# 105358-3SC001-01-A_PWR_MGMT.net
KiCad netlist of a schematic drawn in Altium Designer
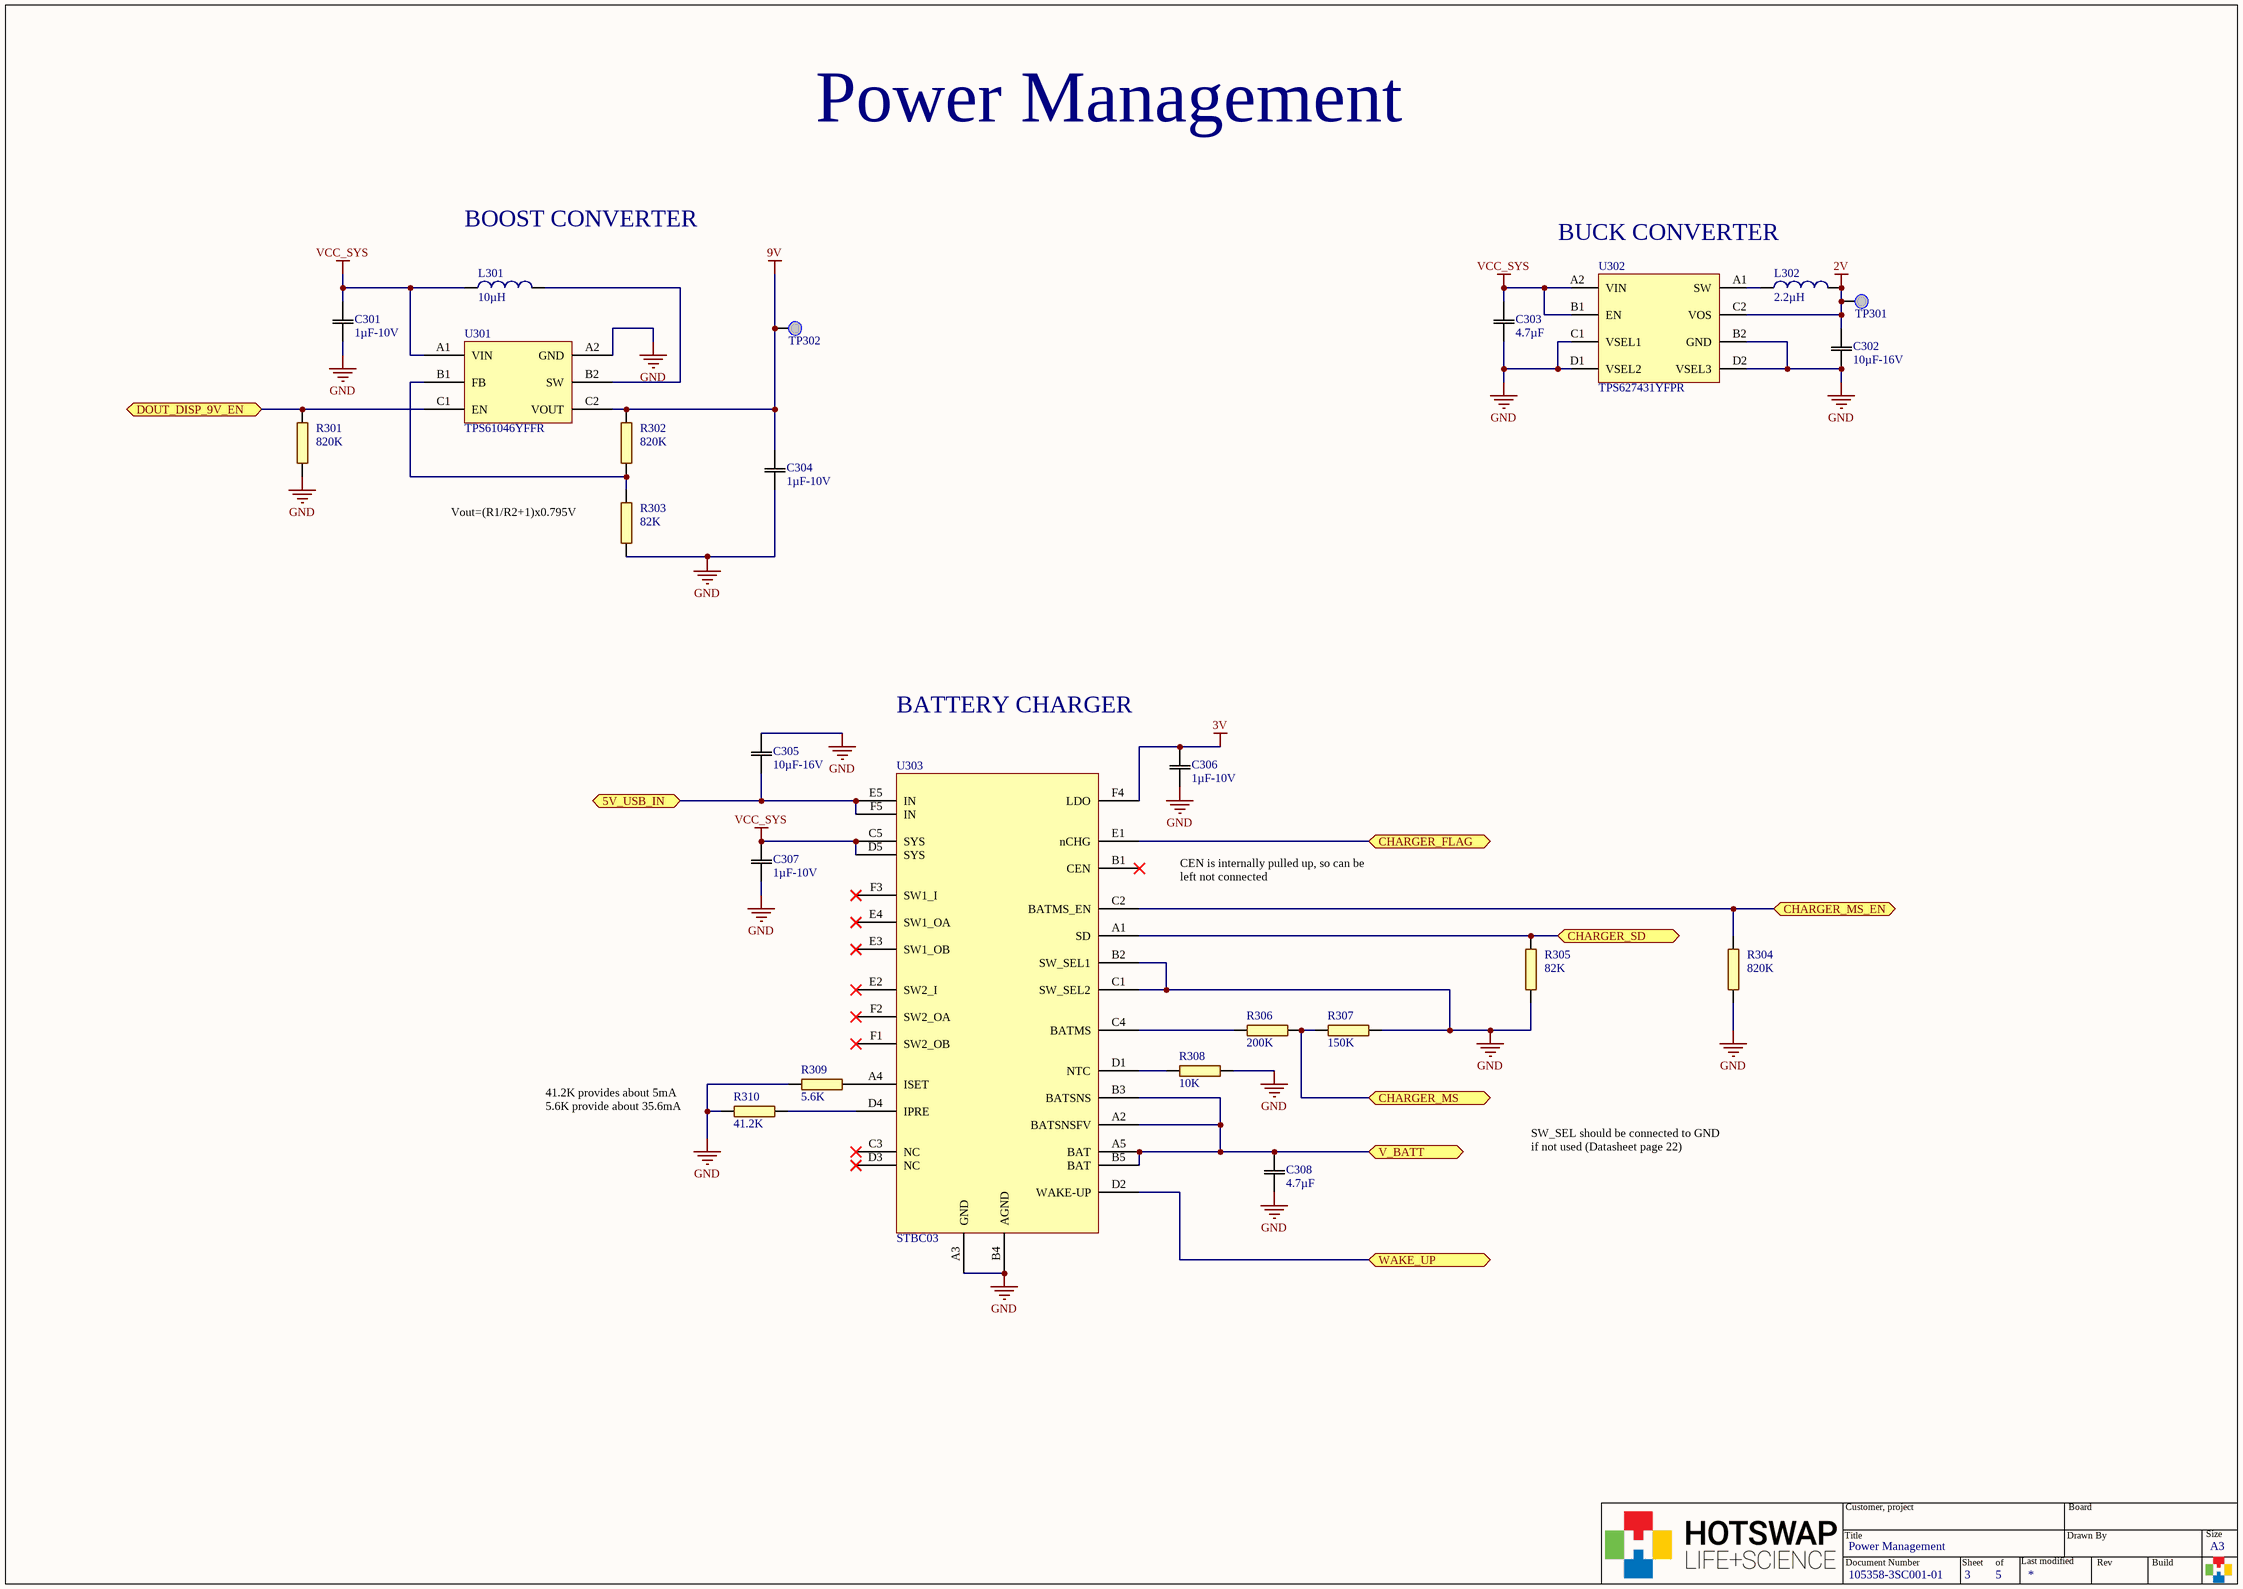
[diagram p0: 105358-3SC001-01-A_PWR_MGMT.SchDoc]

(export (version "E")
  (design (tool "Eeschema 10.0.6"))
  (components
    (comp (ref "C301")
      (value "1µF-10V")
      (footprint "0402C_HIGH_DENSITY")
      (description "1µF ±10% 10V X5R Ceramic Capacitor 0402")
      (fields
        (field (name "MANUFACTURER PART NUMBER") "CC0402KRX5R6BB105")
        (field (name "MANUFACTURER") "Yageo")
      )
      (libsource (lib "ConnectMedical") (part "0402C-1uF-10V"))
    )
    (comp (ref "C302")
      (value "10µF-16V")
      (footprint "0603C_HIGH_DENSITY")
      (description "16µF ±10% 16V X5R Ceramic Capacitor 0603")
      (fields
        (field (name "MANUFACTURER PART NUMBER") "GRT188R61C106KE13D")
        (field (name "MANUFACTURER") "Murata Electronics North America")
      )
      (libsource (lib "ConnectMedical") (part "0603C-10uF-16V"))
    )
    (comp (ref "C303")
      (value "4.7µF")
      (footprint "0402C_HIGH_DENSITY")
      (description "4.7µF ±10% 6.3V X5R Ceramic Capacitor 0402")
      (fields
        (field (name "MANUFACTURER PART NUMBER") "C1005X5R0J475K050BC")
        (field (name "MANUFACTURER") "TDK Corporation")
      )
      (libsource (lib "ConnectMedical") (part "0402C-4.7uF-6.3V"))
    )
    (comp (ref "C304")
      (value "1µF-10V")
      (footprint "0402C_HIGH_DENSITY")
      (description "1µF ±10% 10V X5R Ceramic Capacitor 0402")
      (fields
        (field (name "MANUFACTURER PART NUMBER") "CC0402KRX5R6BB105")
        (field (name "MANUFACTURER") "Yageo")
      )
      (libsource (lib "ConnectMedical") (part "0402C-1uF-10V"))
    )
    (comp (ref "C305")
      (value "10µF-16V")
      (footprint "0603C_HIGH_DENSITY")
      (description "16µF ±10% 16V X5R Ceramic Capacitor 0603")
      (fields
        (field (name "MANUFACTURER PART NUMBER") "GRT188R61C106KE13D")
        (field (name "MANUFACTURER") "Murata Electronics North America")
      )
      (libsource (lib "ConnectMedical") (part "0603C-10uF-16V"))
    )
    (comp (ref "C306")
      (value "1µF-10V")
      (footprint "0402C_HIGH_DENSITY")
      (description "1µF ±10% 10V X5R Ceramic Capacitor 0402")
      (fields
        (field (name "MANUFACTURER PART NUMBER") "CC0402KRX5R6BB105")
        (field (name "MANUFACTURER") "Yageo")
      )
      (libsource (lib "ConnectMedical") (part "0402C-1uF-10V"))
    )
    (comp (ref "C307")
      (value "1µF-10V")
      (footprint "0402C_HIGH_DENSITY")
      (description "1µF ±10% 10V X5R Ceramic Capacitor 0402")
      (fields
        (field (name "MANUFACTURER PART NUMBER") "CC0402KRX5R6BB105")
        (field (name "MANUFACTURER") "Yageo")
      )
      (libsource (lib "ConnectMedical") (part "0402C-1uF-10V"))
    )
    (comp (ref "C308")
      (value "4.7µF")
      (footprint "0402C_HIGH_DENSITY")
      (description "4.7µF ±10% 6.3V X5R Ceramic Capacitor 0402")
      (fields
        (field (name "MANUFACTURER PART NUMBER") "C1005X5R0J475K050BC")
        (field (name "MANUFACTURER") "TDK Corporation")
      )
      (libsource (lib "ConnectMedical") (part "0402C-4.7uF-6.3V"))
    )
    (comp (ref "L301")
      (value "10µH")
      (footprint "0805L_HIGH_DENSITY")
      (description "FIXED IND 10UH 500MA 300 MOHM")
      (fields
        (field (name "DIGI-KEY PART NUMBER") "445-6762-1-ND")
        (field (name "MANUFACTURER") "TDK Corporation")
      )
      (libsource (lib "ConnectMedical") (part "0805L-10uH-0.39Ohm"))
    )
    (comp (ref "L302")
      (value "2.2µH")
      (footprint "0805L_HIGH_DENSITY")
      (description "FIXED IND 2.2UH 600MA 0.2OHM SMD")
      (fields
        (field (name "DIGI-KEY PART NUMBER") "445-17077-1-ND")
        (field (name "MANUFACTURER") "TDK Corporation")
      )
      (libsource (lib "ConnectMedical") (part "0805L-2.2uH-0.2Ohm"))
    )
    (comp (ref "R301")
      (value "820K")
      (footprint "0402R-GENERIC")
      (description "RES SMD 820kOHM 1% 1/16W 0402")
      (fields (field (name "DIGI-KEY PART NUMBER") "YAG3240CT-ND") (field (name "MANUFACTURER") "Yageo"))
      (libsource (lib "ConnectMedical") (part "0402R-820k OHM-1%-0.063W"))
    )
    (comp (ref "R302")
      (value "820K")
      (footprint "0402R-GENERIC")
      (description "RES SMD 820kOHM 1% 1/16W 0402")
      (fields (field (name "DIGI-KEY PART NUMBER") "YAG3240CT-ND") (field (name "MANUFACTURER") "Yageo"))
      (libsource (lib "ConnectMedical") (part "0402R-820k OHM-1%-0.063W"))
    )
    (comp (ref "R303")
      (value "82K")
      (footprint "0402R-GENERIC")
      (description "RES SMD 82kOHM 1% 1/16W 0402")
      (fields (field (name "DIGI-KEY PART NUMBER") "311-82.0KLRCT-ND") (field (name "MANUFACTURER") "Yageo"))
      (libsource (lib "ConnectMedical") (part "0402R-82k OHM-1%-0.063W"))
    )
    (comp (ref "R304")
      (value "820K")
      (footprint "0402R-GENERIC")
      (description "RES SMD 820kOHM 1% 1/16W 0402")
      (fields (field (name "DIGI-KEY PART NUMBER") "YAG3240CT-ND") (field (name "MANUFACTURER") "Yageo"))
      (libsource (lib "ConnectMedical") (part "0402R-820k OHM-1%-0.063W"))
    )
    (comp (ref "R305")
      (value "82K")
      (footprint "0402R-GENERIC")
      (description "RES SMD 82kOHM 1% 1/16W 0402")
      (fields (field (name "DIGI-KEY PART NUMBER") "311-82.0KLRCT-ND") (field (name "MANUFACTURER") "Yageo"))
      (libsource (lib "ConnectMedical") (part "0402R-82k OHM-1%-0.063W"))
    )
    (comp (ref "R306")
      (value "200K")
      (footprint "0402R-GENERIC")
      (description "RES SMD 200kOHM 1% 1/16W 0402")
      (fields (field (name "DIGI-KEY PART NUMBER") "YAG3452CT-ND") (field (name "MANUFACTURER") "Yageo"))
      (libsource (lib "ConnectMedical") (part "0402R-200k OHM-1%-0.063W"))
    )
    (comp (ref "R307")
      (value "150K")
      (footprint "0402R-GENERIC")
      (description "RES SMD 150kOHM 5% 1/16W 0402")
      (fields (field (name "DIGI-KEY PART NUMBER") "311-150KJRCT-ND") (field (name "MANUFACTURER") "Yageo"))
      (libsource (lib "ConnectMedical") (part "0402R-150k OHM-5%-0.063W"))
    )
    (comp (ref "R308")
      (value "10K")
      (footprint "0402R-GENERIC")
      (description "RES SMD 10kOHM 1% 1/16W 0402")
      (fields (field (name "DIGI-KEY PART NUMBER") "311-10.0KLRCT-ND") (field (name "MANUFACTURER") "Yageo"))
      (libsource (lib "ConnectMedical") (part "0402R-10k OHM-1%-0.063W"))
    )
    (comp (ref "R309")
      (value "5.6K")
      (footprint "0402R-GENERIC")
      (description "RES SMD 5.6kOHM 5% 1/16W 0402")
      (fields (field (name "DIGI-KEY PART NUMBER") "311-5.6KJRCT-ND") (field (name "MANUFACTURER") "Yageo"))
      (libsource (lib "ConnectMedical") (part "0402R-5.6k OHM-5%-0.063W"))
    )
    (comp (ref "R310")
      (value "41.2K")
      (footprint "0402R-GENERIC")
      (description "RES SMD 41.2kOHM 1% 1/16W 0402")
      (fields (field (name "DIGI-KEY PART NUMBER") "YAG3155CT-ND") (field (name "MANUFACTURER") "Yageo"))
      (libsource (lib "ConnectMedical") (part "0402R-41.2k OHM-1%-0.063W"))
    )
    (comp (ref "TP301")
      (value "TEST POINT")
      (footprint "PAD TEST POINT")
      (description "Testing Poiny")
      (libsource (lib "ConnectMedical") (part "TEST POINT"))
    )
    (comp (ref "TP302")
      (value "TEST POINT")
      (footprint "PAD TEST POINT")
      (description "Testing Poiny")
      (libsource (lib "ConnectMedical") (part "TEST POINT"))
    )
    (comp (ref "U301")
      (value "TPS61046YFFR")
      (footprint "TPS61046YFFR")
      (description "Boost converter 28V")
      (fields
        (field (name "MANUFACTURER") "Texas Instruments")
        (field (name "DIGI-KEY PART NUMBER") "296-44337-1-ND")
      )
      (libsource (lib "ConnectMedical") (part "TPS61046YFFR"))
    )
    (comp (ref "U302")
      (value "TPS627431YFPR")
      (footprint "TPS627431YFPR")
      (description "Buck Converter")
      (fields
        (field (name "MANUFACTURER") "Texas Instruments")
        (field (name "DIGI-KEY PART NUMBER") "296-44499-2-ND")
      )
      (libsource (lib "ConnectMedical") (part "TPS627431YFPR"))
    )
    (comp (ref "U303")
      (value "STBC03")
      (footprint "STBC03")
      (description "Li-Ion linear battery charger")
      (fields
        (field (name "MANUFACTURER PART NUMBER") "STBC03JR")
        (field (name "MANUFACTURER") "STMicroelectronics")
      )
      (libsource (lib "ConnectMedical") (part "STBC03"))
    )
  )
  (nets
    (net (code "1") (name "/5V_USB_IN") (class "Default")
      (node (ref "C305") (pin "1") (pinfunction "1_1") (pintype "passive"))
      (node (ref "U303") (pin "E5") (pinfunction "IN_E5") (pintype "passive"))
      (node (ref "U303") (pin "F5") (pinfunction "IN_F5") (pintype "passive"))
    )
    (net (code "2") (name "/CHARGER_FLAG") (class "Default")
      (node (ref "U303") (pin "E1") (pinfunction "nCHG_E1") (pintype "passive"))
    )
    (net (code "3") (name "/CHARGER_MS") (class "Default")
      (node (ref "R306") (pin "2") (pintype "passive"))
      (node (ref "R307") (pin "1") (pintype "passive"))
    )
    (net (code "4") (name "/CHARGER_MS_EN") (class "Default")
      (node (ref "R304") (pin "1") (pintype "passive"))
      (node (ref "U303") (pin "C2") (pinfunction "BATMS_EN_C2") (pintype "passive"))
    )
    (net (code "5") (name "/CHARGER_SD") (class "Default")
      (node (ref "R305") (pin "1") (pintype "passive"))
      (node (ref "U303") (pin "A1") (pinfunction "SD_A1") (pintype "passive"))
    )
    (net (code "6") (name "/DOUT_DISP_9V_EN") (class "Default")
      (node (ref "R301") (pin "1") (pintype "passive"))
      (node (ref "U301") (pin "C1") (pinfunction "EN_C1") (pintype "passive"))
    )
    (net (code "7") (name "/V_BATT") (class "Default")
      (node (ref "C308") (pin "2") (pinfunction "2_2") (pintype "passive"))
      (node (ref "U303") (pin "A2") (pinfunction "BATSNSFV_A2") (pintype "passive"))
      (node (ref "U303") (pin "A5") (pinfunction "BAT_A5") (pintype "passive"))
      (node (ref "U303") (pin "B3") (pinfunction "BATSNS_B3") (pintype "passive"))
      (node (ref "U303") (pin "B5") (pinfunction "BAT_B5") (pintype "passive"))
    )
    (net (code "8") (name "/WAKE_UP") (class "Default")
      (node (ref "U303") (pin "D2") (pinfunction "WAKE-UP_D2") (pintype "passive"))
    )
    (net (code "9") (name "2V") (class "Default")
      (node (ref "C302") (pin "2") (pinfunction "2_2") (pintype "passive"))
      (node (ref "L302") (pin "2") (pinfunction "2_2") (pintype "passive"))
      (node (ref "TP301") (pin "1") (pinfunction "Test_Point_1") (pintype "passive"))
      (node (ref "U302") (pin "C2") (pinfunction "VOS_C2") (pintype "passive"))
    )
    (net (code "10") (name "3V") (class "Default")
      (node (ref "C306") (pin "2") (pinfunction "2_2") (pintype "passive"))
      (node (ref "U303") (pin "F4") (pinfunction "LDO_F4") (pintype "passive"))
    )
    (net (code "11") (name "9V") (class "Default")
      (node (ref "C304") (pin "2") (pinfunction "2_2") (pintype "passive"))
      (node (ref "R302") (pin "1") (pintype "passive"))
      (node (ref "TP302") (pin "1") (pinfunction "Test_Point_1") (pintype "passive"))
      (node (ref "U301") (pin "C2") (pinfunction "VOUT_C2") (pintype "passive"))
    )
    (net (code "12") (name "GND") (class "Default")
      (node (ref "C301") (pin "1") (pinfunction "1_1") (pintype "passive"))
      (node (ref "C302") (pin "1") (pinfunction "1_1") (pintype "passive"))
      (node (ref "C303") (pin "1") (pinfunction "1_1") (pintype "passive"))
      (node (ref "C304") (pin "1") (pinfunction "1_1") (pintype "passive"))
      (node (ref "C305") (pin "2") (pinfunction "2_2") (pintype "passive"))
      (node (ref "C306") (pin "1") (pinfunction "1_1") (pintype "passive"))
      (node (ref "C307") (pin "1") (pinfunction "1_1") (pintype "passive"))
      (node (ref "C308") (pin "1") (pinfunction "1_1") (pintype "passive"))
      (node (ref "R301") (pin "2") (pintype "passive"))
      (node (ref "R303") (pin "2") (pintype "passive"))
      (node (ref "R304") (pin "2") (pintype "passive"))
      (node (ref "R305") (pin "2") (pintype "passive"))
      (node (ref "R307") (pin "2") (pintype "passive"))
      (node (ref "R308") (pin "2") (pintype "passive"))
      (node (ref "R309") (pin "1") (pintype "passive"))
      (node (ref "R310") (pin "1") (pintype "passive"))
      (node (ref "U301") (pin "A2") (pinfunction "GND_A2") (pintype "passive"))
      (node (ref "U302") (pin "B2") (pinfunction "GND_B2") (pintype "passive"))
      (node (ref "U302") (pin "C1") (pinfunction "VSEL1_C1") (pintype "passive"))
      (node (ref "U302") (pin "D1") (pinfunction "VSEL2_D1") (pintype "passive"))
      (node (ref "U302") (pin "D2") (pinfunction "VSEL3_D2") (pintype "passive"))
      (node (ref "U303") (pin "A3") (pinfunction "GND_A3") (pintype "passive"))
      (node (ref "U303") (pin "B2") (pinfunction "SW_SEL1_B2") (pintype "passive"))
      (node (ref "U303") (pin "B4") (pinfunction "AGND_B4") (pintype "passive"))
      (node (ref "U303") (pin "C1") (pinfunction "SW_SEL2_C1") (pintype "passive"))
    )
    (net (code "13") (name "Net-(U301-FB)") (class "Default")
      (node (ref "R302") (pin "2") (pintype "passive"))
      (node (ref "R303") (pin "1") (pintype "passive"))
      (node (ref "U301") (pin "B1") (pinfunction "FB_B1") (pintype "passive"))
    )
    (net (code "14") (name "Net-(U301-SW)") (class "Default")
      (node (ref "L301") (pin "2") (pinfunction "2_2") (pintype "passive"))
      (node (ref "U301") (pin "B2") (pinfunction "SW_B2") (pintype "passive"))
    )
    (net (code "15") (name "Net-(U302-SW)") (class "Default")
      (node (ref "L302") (pin "1") (pinfunction "1_1") (pintype "passive"))
      (node (ref "U302") (pin "A1") (pinfunction "SW_A1") (pintype "passive"))
    )
    (net (code "16") (name "Net-(U303-BATMS)") (class "Default")
      (node (ref "R306") (pin "1") (pintype "passive"))
      (node (ref "U303") (pin "C4") (pinfunction "BATMS_C4") (pintype "passive"))
    )
    (net (code "17") (name "Net-(U303-IPRE)") (class "Default")
      (node (ref "R310") (pin "2") (pintype "passive"))
      (node (ref "U303") (pin "D4") (pinfunction "IPRE_D4") (pintype "passive"))
    )
    (net (code "18") (name "Net-(U303-ISET)") (class "Default")
      (node (ref "R309") (pin "2") (pintype "passive"))
      (node (ref "U303") (pin "A4") (pinfunction "ISET_A4") (pintype "passive"))
    )
    (net (code "19") (name "Net-(U303-NTC)") (class "Default")
      (node (ref "R308") (pin "1") (pintype "passive"))
      (node (ref "U303") (pin "D1") (pinfunction "NTC_D1") (pintype "passive"))
    )
    (net (code "20") (name "VCC_SYS") (class "Default")
      (node (ref "C301") (pin "2") (pinfunction "2_2") (pintype "passive"))
      (node (ref "C303") (pin "2") (pinfunction "2_2") (pintype "passive"))
      (node (ref "C307") (pin "2") (pinfunction "2_2") (pintype "passive"))
      (node (ref "L301") (pin "1") (pinfunction "1_1") (pintype "passive"))
      (node (ref "U301") (pin "A1") (pinfunction "VIN_A1") (pintype "passive"))
      (node (ref "U302") (pin "A2") (pinfunction "VIN_A2") (pintype "passive"))
      (node (ref "U302") (pin "B1") (pinfunction "EN_B1") (pintype "passive"))
      (node (ref "U303") (pin "C5") (pinfunction "SYS_C5") (pintype "passive"))
      (node (ref "U303") (pin "D5") (pinfunction "SYS_D5") (pintype "passive"))
    )
    (net (code "21") (name "unconnected-(U303-CEN-PadB1)") (class "Default")
      (node (ref "U303") (pin "B1") (pinfunction "CEN_B1") (pintype "passive+no_connect"))
    )
    (net (code "22") (name "unconnected-(U303-NC-PadC3)") (class "Default")
      (node (ref "U303") (pin "C3") (pinfunction "NC_C3") (pintype "passive+no_connect"))
    )
    (net (code "23") (name "unconnected-(U303-NC-PadD3)") (class "Default")
      (node (ref "U303") (pin "D3") (pinfunction "NC_D3") (pintype "passive+no_connect"))
    )
    (net (code "24") (name "unconnected-(U303-SW1_I-PadF3)") (class "Default")
      (node (ref "U303") (pin "F3") (pinfunction "SW1_I_F3") (pintype "passive+no_connect"))
    )
    (net (code "25") (name "unconnected-(U303-SW1_OA-PadE4)") (class "Default")
      (node (ref "U303") (pin "E4") (pinfunction "SW1_OA_E4") (pintype "passive+no_connect"))
    )
    (net (code "26") (name "unconnected-(U303-SW1_OB-PadE3)") (class "Default")
      (node (ref "U303") (pin "E3") (pinfunction "SW1_OB_E3") (pintype "passive+no_connect"))
    )
    (net (code "27") (name "unconnected-(U303-SW2_I-PadE2)") (class "Default")
      (node (ref "U303") (pin "E2") (pinfunction "SW2_I_E2") (pintype "passive+no_connect"))
    )
    (net (code "28") (name "unconnected-(U303-SW2_OA-PadF2)") (class "Default")
      (node (ref "U303") (pin "F2") (pinfunction "SW2_OA_F2") (pintype "passive+no_connect"))
    )
    (net (code "29") (name "unconnected-(U303-SW2_OB-PadF1)") (class "Default")
      (node (ref "U303") (pin "F1") (pinfunction "SW2_OB_F1") (pintype "passive+no_connect"))
    )
  )
)
